# Frisbee.net
KiCad netlist of a schematic drawn in EAGLE
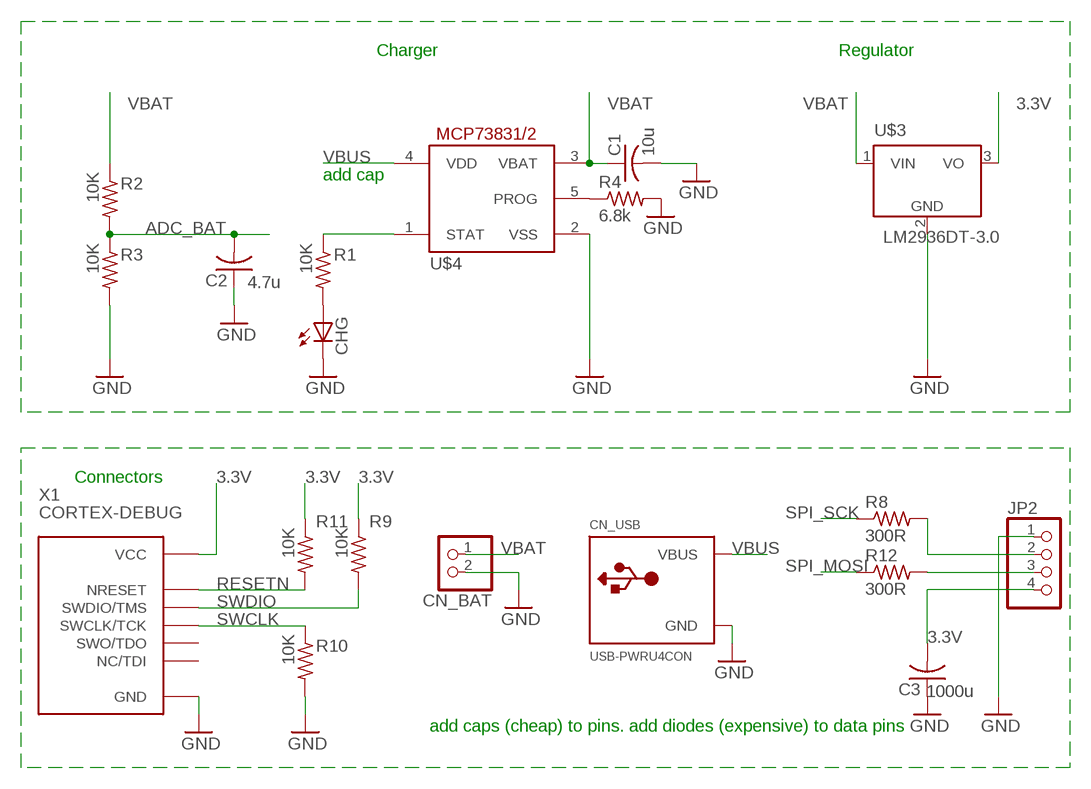
[diagram p0: schematic, sheet 1]
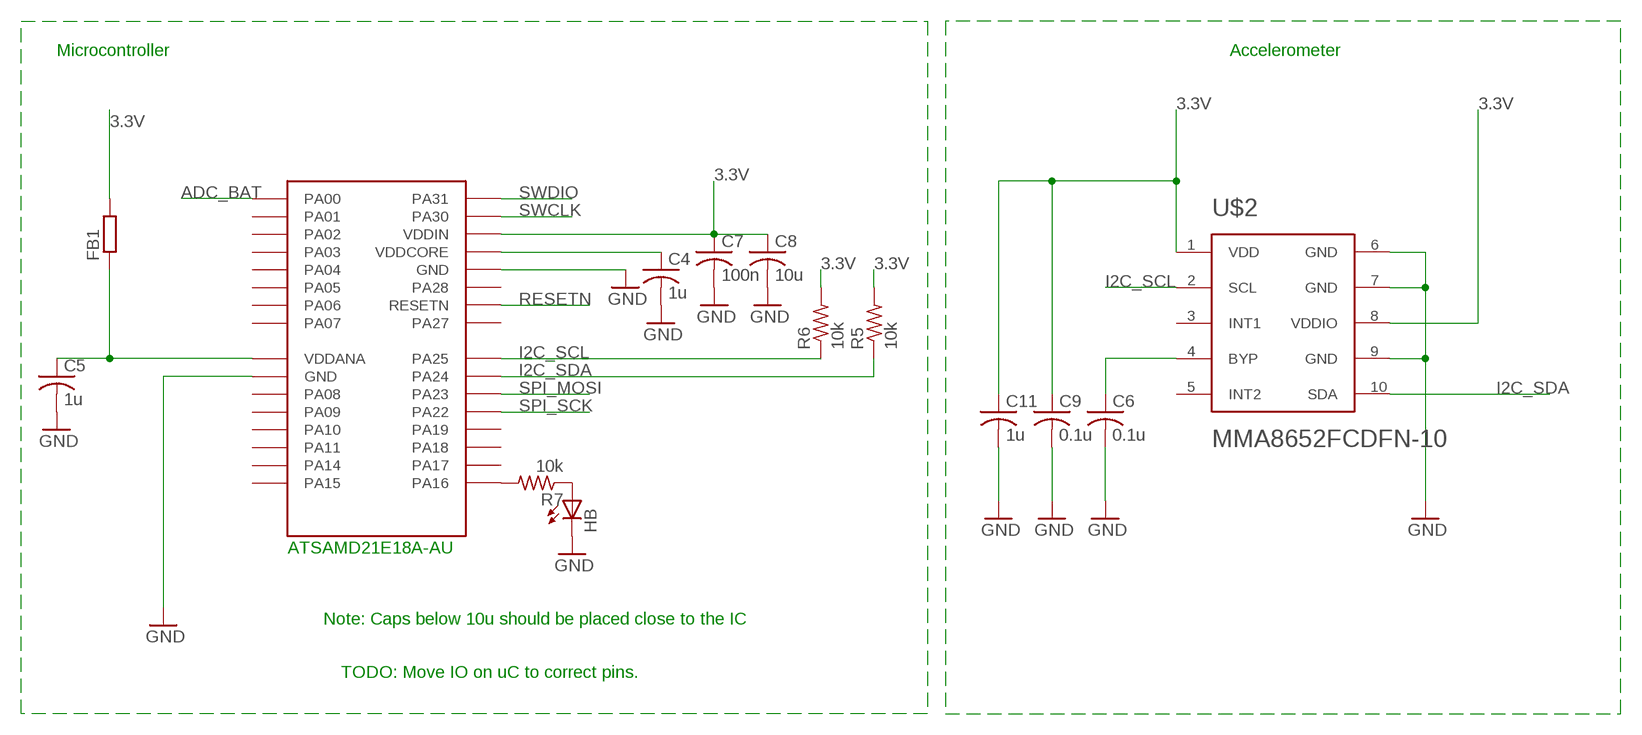
[diagram p1: schematic, sheet 2]

(export (version "E")
  (design (tool "Eeschema 10.0.6"))
  (components
    (comp (ref "C4")
      (value "1u")
      (footprint "eagle-import:C0603")
      (libsource (lib "eagle-import") (part "C-USC0603"))
    )
    (comp (ref "C5")
      (value "1u")
      (footprint "eagle-import:C0603")
      (libsource (lib "eagle-import") (part "C-USC0603"))
    )
    (comp (ref "C6")
      (value "0.1u")
      (footprint "eagle-import:C0603")
      (libsource (lib "eagle-import") (part "C-USC0603"))
    )
    (comp (ref "C7")
      (value "100n")
      (footprint "eagle-import:C0603")
      (libsource (lib "eagle-import") (part "C-USC0603"))
    )
    (comp (ref "C8")
      (value "10u")
      (footprint "eagle-import:C0603")
      (libsource (lib "eagle-import") (part "C-USC0603"))
    )
    (comp (ref "C9")
      (value "0.1u")
      (footprint "eagle-import:C0603")
      (libsource (lib "eagle-import") (part "C-USC0603"))
    )
    (comp (ref "C11")
      (value "1u")
      (footprint "eagle-import:C0603")
      (libsource (lib "eagle-import") (part "C-USC0603"))
    )
    (comp (ref "FB1")
      (value "R-EU_M0805")
      (footprint "eagle-import:M0805")
      (libsource (lib "eagle-import") (part "R-EU_M0805"))
    )
    (comp (ref "HB")
      (value "LEDCHIPLED_0603")
      (footprint "eagle-import:CHIPLED_0603")
      (libsource (lib "eagle-import") (part "LEDCHIPLED_0603"))
    )
    (comp (ref "R5")
      (value "10k")
      (footprint "eagle-import:R0603")
      (libsource (lib "eagle-import") (part "R-US_R0603"))
    )
    (comp (ref "R6")
      (value "10k")
      (footprint "eagle-import:R0603")
      (libsource (lib "eagle-import") (part "R-US_R0603"))
    )
    (comp (ref "R7")
      (value "10k")
      (footprint "eagle-import:R0603")
      (libsource (lib "eagle-import") (part "R-US_R0603"))
    )
    (comp (ref "U$1")
      (value "ATSAMD21E18A-AU")
      (footprint "eagle-import:32-TQFP")
      (libsource (lib "eagle-import") (part "ATSAMD21E18A-AU"))
    )
    (comp (ref "U$2")
      (value "MMA8652FCDFN-10")
      (footprint "eagle-import:DFN-10")
      (libsource (lib "eagle-import") (part "MMA8652FCDFN-10"))
    )
    (comp (ref "C1")
      (value "10u")
      (footprint "eagle-import:C0805")
      (libsource (lib "eagle-import") (part "C-USC0805"))
    )
    (comp (ref "C2")
      (value "4.7u")
      (footprint "eagle-import:C0805")
      (libsource (lib "eagle-import") (part "C-USC0805"))
    )
    (comp (ref "C3")
      (value "1000u")
      (footprint "eagle-import:C0805")
      (libsource (lib "eagle-import") (part "C-USC0805"))
    )
    (comp (ref "CHG")
      (value "LEDCHIP-LED0603")
      (footprint "eagle-import:CHIP-LED0603")
      (libsource (lib "eagle-import") (part "LEDCHIP-LED0603"))
    )
    (comp (ref "CN_BAT")
      (value "JST_2PIN-SMT-RA")
      (footprint "eagle-import:JST-PH-2-SMT-RA")
      (libsource (lib "eagle-import") (part "JST_2PIN-SMT-RA"))
    )
    (comp (ref "CN_USB")
      (value "USB-PWRU4CON")
      (footprint "eagle-import:USB-MINIB-THM-PWRONLY")
      (libsource (lib "eagle-import") (part "USB-PWRU4CON"))
    )
    (comp (ref "JP2")
      (value "PINHD-1X4/90")
      (footprint "eagle-import:1X04_90")
      (libsource (lib "eagle-import") (part "PINHD-1X4/90"))
    )
    (comp (ref "R1")
      (value "10K")
      (footprint "eagle-import:R0603")
      (libsource (lib "eagle-import") (part "R-US_R0603"))
    )
    (comp (ref "R2")
      (value "10K")
      (footprint "eagle-import:R0603")
      (libsource (lib "eagle-import") (part "R-US_R0603"))
    )
    (comp (ref "R3")
      (value "10K")
      (footprint "eagle-import:R0603")
      (libsource (lib "eagle-import") (part "R-US_R0603"))
    )
    (comp (ref "R4")
      (value "6.8k")
      (footprint "eagle-import:R0805")
      (libsource (lib "eagle-import") (part "R-US_R0805"))
    )
    (comp (ref "R8")
      (value "300R")
      (footprint "eagle-import:R0805")
      (libsource (lib "eagle-import") (part "R-US_R0805"))
    )
    (comp (ref "R9")
      (value "10K")
      (footprint "eagle-import:R0603")
      (libsource (lib "eagle-import") (part "R-US_R0603"))
    )
    (comp (ref "R10")
      (value "10K")
      (footprint "eagle-import:R0603")
      (libsource (lib "eagle-import") (part "R-US_R0603"))
    )
    (comp (ref "R11")
      (value "10K")
      (footprint "eagle-import:R0603")
      (libsource (lib "eagle-import") (part "R-US_R0603"))
    )
    (comp (ref "R12")
      (value "300R")
      (footprint "eagle-import:R0805")
      (libsource (lib "eagle-import") (part "R-US_R0805"))
    )
    (comp (ref "U$3")
      (value "LM2936DT-3.0")
      (footprint "eagle-import:TO252")
      (fields (field (name "MF") "NATIONAL SEMICONDUCTOR"))
      (libsource (lib "eagle-import") (part "LM2936?DT-3.0"))
    )
    (comp (ref "U$4")
      (value "MCP73831/OT")
      (footprint "eagle-import:SOT23-5L")
      (libsource (lib "eagle-import") (part "MCP73831/OT"))
    )
    (comp (ref "X1")
      (value "CORTEX-DEBUG")
      (footprint "eagle-import:CORTEX-DEBUG")
      (libsource (lib "eagle-import") (part "CORTEX-DEBUG"))
    )
  )
  (nets
    (net (code "1") (name "3.3V") (class "Default")
      (node (ref "C11") (pin "1") (pinfunction "1_1") (pintype "passive"))
      (node (ref "C3") (pin "2") (pinfunction "2_2") (pintype "passive"))
      (node (ref "C7") (pin "1") (pinfunction "1_1") (pintype "passive"))
      (node (ref "C8") (pin "1") (pinfunction "1_1") (pintype "passive"))
      (node (ref "C9") (pin "1") (pinfunction "1_1") (pintype "passive"))
      (node (ref "FB1") (pin "2") (pinfunction "2_2") (pintype "passive"))
      (node (ref "JP2") (pin "4") (pinfunction "4_4") (pintype "passive"))
      (node (ref "R11") (pin "1") (pinfunction "1_1") (pintype "passive"))
      (node (ref "R5") (pin "2") (pinfunction "2_2") (pintype "passive"))
      (node (ref "R6") (pin "2") (pinfunction "2_2") (pintype "passive"))
      (node (ref "R9") (pin "1") (pinfunction "1_1") (pintype "passive"))
      (node (ref "U$1") (pin "30") (pinfunction "VDDIN_30") (pintype "bidirectional"))
      (node (ref "U$2") (pin "1") (pinfunction "VDD_1") (pintype "bidirectional"))
      (node (ref "U$2") (pin "8") (pinfunction "VDDIO_8") (pintype "bidirectional"))
      (node (ref "U$3") (pin "3") (pinfunction "VO_3") (pintype "passive"))
      (node (ref "X1") (pin "VCC") (pinfunction "VCC_VCC") (pintype "bidirectional"))
    )
    (net (code "2") (name "ADC_BAT") (class "Default")
      (node (ref "C2") (pin "2") (pinfunction "2_2") (pintype "passive"))
      (node (ref "R2") (pin "2") (pinfunction "2_2") (pintype "passive"))
      (node (ref "R3") (pin "1") (pinfunction "1_1") (pintype "passive"))
      (node (ref "U$1") (pin "1") (pinfunction "PA00_1") (pintype "bidirectional"))
    )
    (net (code "3") (name "GND") (class "Default")
      (node (ref "C1") (pin "2") (pinfunction "2_2") (pintype "passive"))
      (node (ref "C11") (pin "2") (pinfunction "2_2") (pintype "passive"))
      (node (ref "C2") (pin "1") (pinfunction "1_1") (pintype "passive"))
      (node (ref "C3") (pin "1") (pinfunction "1_1") (pintype "passive"))
      (node (ref "C4") (pin "2") (pinfunction "2_2") (pintype "passive"))
      (node (ref "C5") (pin "2") (pinfunction "2_2") (pintype "passive"))
      (node (ref "C6") (pin "2") (pinfunction "2_2") (pintype "passive"))
      (node (ref "C7") (pin "2") (pinfunction "2_2") (pintype "passive"))
      (node (ref "C8") (pin "2") (pinfunction "2_2") (pintype "passive"))
      (node (ref "C9") (pin "2") (pinfunction "2_2") (pintype "passive"))
      (node (ref "CHG") (pin "C") (pinfunction "C_C") (pintype "passive"))
      (node (ref "CN_BAT") (pin "2") (pinfunction "1_2") (pintype "passive"))
      (node (ref "CN_USB") (pin "GND") (pinfunction "GND_GND") (pintype "power_in"))
      (node (ref "HB") (pin "C") (pinfunction "C_C") (pintype "passive"))
      (node (ref "JP2") (pin "1") (pinfunction "1_1") (pintype "passive"))
      (node (ref "R10") (pin "2") (pinfunction "2_2") (pintype "passive"))
      (node (ref "R3") (pin "2") (pinfunction "2_2") (pintype "passive"))
      (node (ref "R4") (pin "2") (pinfunction "2_2") (pintype "passive"))
      (node (ref "U$1") (pin "10") (pinfunction "GND_10") (pintype "bidirectional"))
      (node (ref "U$1") (pin "28") (pinfunction "GND_28") (pintype "bidirectional"))
      (node (ref "U$2") (pin "6") (pinfunction "GND_6") (pintype "bidirectional"))
      (node (ref "U$2") (pin "7") (pinfunction "GND_7") (pintype "bidirectional"))
      (node (ref "U$2") (pin "9") (pinfunction "GND_9") (pintype "bidirectional"))
      (node (ref "U$3") (pin "2") (pinfunction "GND_2") (pintype "passive"))
      (node (ref "U$4") (pin "2") (pinfunction "VSS_2") (pintype "power_in"))
      (node (ref "X1") (pin "GND1") (pinfunction "GND_GND1") (pintype "bidirectional"))
      (node (ref "X1") (pin "GND2") (pinfunction "GND_GND2") (pintype "bidirectional"))
      (node (ref "X1") (pin "GND_DETECT") (pinfunction "GND_GND_DETECT") (pintype "bidirectional"))
    )
    (net (code "4") (name "I2C_SCL") (class "Default")
      (node (ref "R6") (pin "1") (pinfunction "1_1") (pintype "passive"))
      (node (ref "U$1") (pin "24") (pinfunction "PA25_24") (pintype "bidirectional"))
      (node (ref "U$2") (pin "2") (pinfunction "SCL_2") (pintype "bidirectional"))
    )
    (net (code "5") (name "I2C_SDA") (class "Default")
      (node (ref "R5") (pin "1") (pinfunction "1_1") (pintype "passive"))
      (node (ref "U$1") (pin "23") (pinfunction "PA24_23") (pintype "bidirectional"))
      (node (ref "U$2") (pin "10") (pinfunction "SDA_10") (pintype "bidirectional"))
    )
    (net (code "6") (name "Net-(CHG-PadA)") (class "Default")
      (node (ref "CHG") (pin "A") (pinfunction "A_A") (pintype "passive"))
      (node (ref "R1") (pin "2") (pinfunction "2_2") (pintype "passive"))
    )
    (net (code "7") (name "Net-(HB-PadA)") (class "Default")
      (node (ref "HB") (pin "A") (pinfunction "A_A") (pintype "passive"))
      (node (ref "R7") (pin "1") (pinfunction "1_1") (pintype "passive"))
    )
    (net (code "8") (name "Net-(JP2-Pad2)") (class "Default")
      (node (ref "JP2") (pin "2") (pinfunction "2_2") (pintype "passive"))
      (node (ref "R8") (pin "2") (pinfunction "2_2") (pintype "passive"))
    )
    (net (code "9") (name "Net-(JP2-Pad3)") (class "Default")
      (node (ref "JP2") (pin "3") (pinfunction "3_3") (pintype "passive"))
      (node (ref "R12") (pin "2") (pinfunction "2_2") (pintype "passive"))
    )
    (net (code "10") (name "Net-(U$1-PA16)") (class "Default")
      (node (ref "R7") (pin "2") (pinfunction "2_2") (pintype "passive"))
      (node (ref "U$1") (pin "17") (pinfunction "PA16_17") (pintype "bidirectional"))
    )
    (net (code "11") (name "Net-(U$1-VDDANA)") (class "Default")
      (node (ref "C5") (pin "1") (pinfunction "1_1") (pintype "passive"))
      (node (ref "FB1") (pin "1") (pinfunction "1_1") (pintype "passive"))
      (node (ref "U$1") (pin "9") (pinfunction "VDDANA_9") (pintype "bidirectional"))
    )
    (net (code "12") (name "Net-(U$1-VDDCORE)") (class "Default")
      (node (ref "C4") (pin "1") (pinfunction "1_1") (pintype "passive"))
      (node (ref "U$1") (pin "29") (pinfunction "VDDCORE_29") (pintype "bidirectional"))
    )
    (net (code "13") (name "Net-(U$2-BYP)") (class "Default")
      (node (ref "C6") (pin "1") (pinfunction "1_1") (pintype "passive"))
      (node (ref "U$2") (pin "4") (pinfunction "BYP_4") (pintype "bidirectional"))
    )
    (net (code "14") (name "Net-(U$4-PROG)") (class "Default")
      (node (ref "R4") (pin "1") (pinfunction "1_1") (pintype "passive"))
      (node (ref "U$4") (pin "5") (pinfunction "PROG_5") (pintype "input"))
    )
    (net (code "15") (name "Net-(U$4-STAT)") (class "Default")
      (node (ref "R1") (pin "1") (pinfunction "1_1") (pintype "passive"))
      (node (ref "U$4") (pin "1") (pinfunction "STAT_1") (pintype "output"))
    )
    (net (code "16") (name "RESETN") (class "Default")
      (node (ref "R11") (pin "2") (pinfunction "2_2") (pintype "passive"))
      (node (ref "U$1") (pin "26") (pinfunction "RESETN_26") (pintype "bidirectional"))
      (node (ref "X1") (pin "NRESET") (pinfunction "NRESET_NRESET") (pintype "bidirectional"))
    )
    (net (code "17") (name "SPI_MOSI") (class "Default")
      (node (ref "R12") (pin "1") (pinfunction "1_1") (pintype "passive"))
      (node (ref "U$1") (pin "22") (pinfunction "PA23_22") (pintype "bidirectional"))
    )
    (net (code "18") (name "SPI_SCK") (class "Default")
      (node (ref "R8") (pin "1") (pinfunction "1_1") (pintype "passive"))
      (node (ref "U$1") (pin "21") (pinfunction "PA22_21") (pintype "bidirectional"))
    )
    (net (code "19") (name "SWCLK") (class "Default")
      (node (ref "R10") (pin "1") (pinfunction "1_1") (pintype "passive"))
      (node (ref "U$1") (pin "31") (pinfunction "PA30_31") (pintype "bidirectional"))
      (node (ref "X1") (pin "SWCLK/TCK") (pinfunction "SWCLK/TCK_SWCLK/TCK") (pintype "bidirectional"))
    )
    (net (code "20") (name "SWDIO") (class "Default")
      (node (ref "R9") (pin "2") (pinfunction "2_2") (pintype "passive"))
      (node (ref "U$1") (pin "32") (pinfunction "PA31_32") (pintype "bidirectional"))
      (node (ref "X1") (pin "SWDIO/TMS") (pinfunction "SWDIO/TMS_SWDIO/TMS") (pintype "bidirectional"))
    )
    (net (code "21") (name "VBAT") (class "Default")
      (node (ref "C1") (pin "1") (pinfunction "1_1") (pintype "passive"))
      (node (ref "CN_BAT") (pin "1") (pinfunction "2_1") (pintype "passive"))
      (node (ref "R2") (pin "1") (pinfunction "1_1") (pintype "passive"))
      (node (ref "U$3") (pin "1") (pinfunction "VIN_1") (pintype "input"))
      (node (ref "U$4") (pin "3") (pinfunction "VBAT_3") (pintype "bidirectional"))
    )
    (net (code "22") (name "VBUS") (class "Default")
      (node (ref "CN_USB") (pin "VBUS") (pinfunction "VBUS_VBUS") (pintype "power_in"))
      (node (ref "U$4") (pin "4") (pinfunction "VDD_4") (pintype "power_in"))
    )
    (net (code "23") (name "unconnected-(U$1-PA01-Pad2)") (class "Default")
      (node (ref "U$1") (pin "2") (pinfunction "PA01_2") (pintype "bidirectional"))
    )
    (net (code "24") (name "unconnected-(U$1-PA02-Pad3)") (class "Default")
      (node (ref "U$1") (pin "3") (pinfunction "PA02_3") (pintype "bidirectional"))
    )
    (net (code "25") (name "unconnected-(U$1-PA03-Pad4)") (class "Default")
      (node (ref "U$1") (pin "4") (pinfunction "PA03_4") (pintype "bidirectional"))
    )
    (net (code "26") (name "unconnected-(U$1-PA04-Pad5)") (class "Default")
      (node (ref "U$1") (pin "5") (pinfunction "PA04_5") (pintype "bidirectional"))
    )
    (net (code "27") (name "unconnected-(U$1-PA05-Pad6)") (class "Default")
      (node (ref "U$1") (pin "6") (pinfunction "PA05_6") (pintype "bidirectional"))
    )
    (net (code "28") (name "unconnected-(U$1-PA06-Pad7)") (class "Default")
      (node (ref "U$1") (pin "7") (pinfunction "PA06_7") (pintype "bidirectional"))
    )
    (net (code "29") (name "unconnected-(U$1-PA07-Pad8)") (class "Default")
      (node (ref "U$1") (pin "8") (pinfunction "PA07_8") (pintype "bidirectional"))
    )
    (net (code "30") (name "unconnected-(U$1-PA08-Pad11)") (class "Default")
      (node (ref "U$1") (pin "11") (pinfunction "PA08_11") (pintype "bidirectional"))
    )
    (net (code "31") (name "unconnected-(U$1-PA09-Pad12)") (class "Default")
      (node (ref "U$1") (pin "12") (pinfunction "PA09_12") (pintype "bidirectional"))
    )
    (net (code "32") (name "unconnected-(U$1-PA10-Pad13)") (class "Default")
      (node (ref "U$1") (pin "13") (pinfunction "PA10_13") (pintype "bidirectional"))
    )
    (net (code "33") (name "unconnected-(U$1-PA11-Pad14)") (class "Default")
      (node (ref "U$1") (pin "14") (pinfunction "PA11_14") (pintype "bidirectional"))
    )
    (net (code "34") (name "unconnected-(U$1-PA14-Pad15)") (class "Default")
      (node (ref "U$1") (pin "15") (pinfunction "PA14_15") (pintype "bidirectional"))
    )
    (net (code "35") (name "unconnected-(U$1-PA15-Pad16)") (class "Default")
      (node (ref "U$1") (pin "16") (pinfunction "PA15_16") (pintype "bidirectional"))
    )
    (net (code "36") (name "unconnected-(U$1-PA17-Pad18)") (class "Default")
      (node (ref "U$1") (pin "18") (pinfunction "PA17_18") (pintype "bidirectional"))
    )
    (net (code "37") (name "unconnected-(U$1-PA18-Pad19)") (class "Default")
      (node (ref "U$1") (pin "19") (pinfunction "PA18_19") (pintype "bidirectional"))
    )
    (net (code "38") (name "unconnected-(U$1-PA19-Pad20)") (class "Default")
      (node (ref "U$1") (pin "20") (pinfunction "PA19_20") (pintype "bidirectional"))
    )
    (net (code "39") (name "unconnected-(U$1-PA27-Pad25)") (class "Default")
      (node (ref "U$1") (pin "25") (pinfunction "PA27_25") (pintype "bidirectional"))
    )
    (net (code "40") (name "unconnected-(U$1-PA28-Pad27)") (class "Default")
      (node (ref "U$1") (pin "27") (pinfunction "PA28_27") (pintype "bidirectional"))
    )
    (net (code "41") (name "unconnected-(U$2-INT1-Pad3)") (class "Default")
      (node (ref "U$2") (pin "3") (pinfunction "INT1_3") (pintype "bidirectional"))
    )
    (net (code "42") (name "unconnected-(U$2-INT2-Pad5)") (class "Default")
      (node (ref "U$2") (pin "5") (pinfunction "INT2_5") (pintype "bidirectional"))
    )
    (net (code "43") (name "unconnected-(X1-PadNC{slash}TDI)") (class "Default")
      (node (ref "X1") (pin "NC/TDI") (pinfunction "NC/TDI_NC/TDI") (pintype "bidirectional"))
    )
    (net (code "44") (name "unconnected-(X1-PadSWO{slash}TDO)") (class "Default")
      (node (ref "X1") (pin "SWO/TDO") (pinfunction "SWO/TDO_SWO/TDO") (pintype "bidirectional"))
    )
  )
)
